# Sheet1.net
KiCad netlist of a schematic drawn in Altium Designer
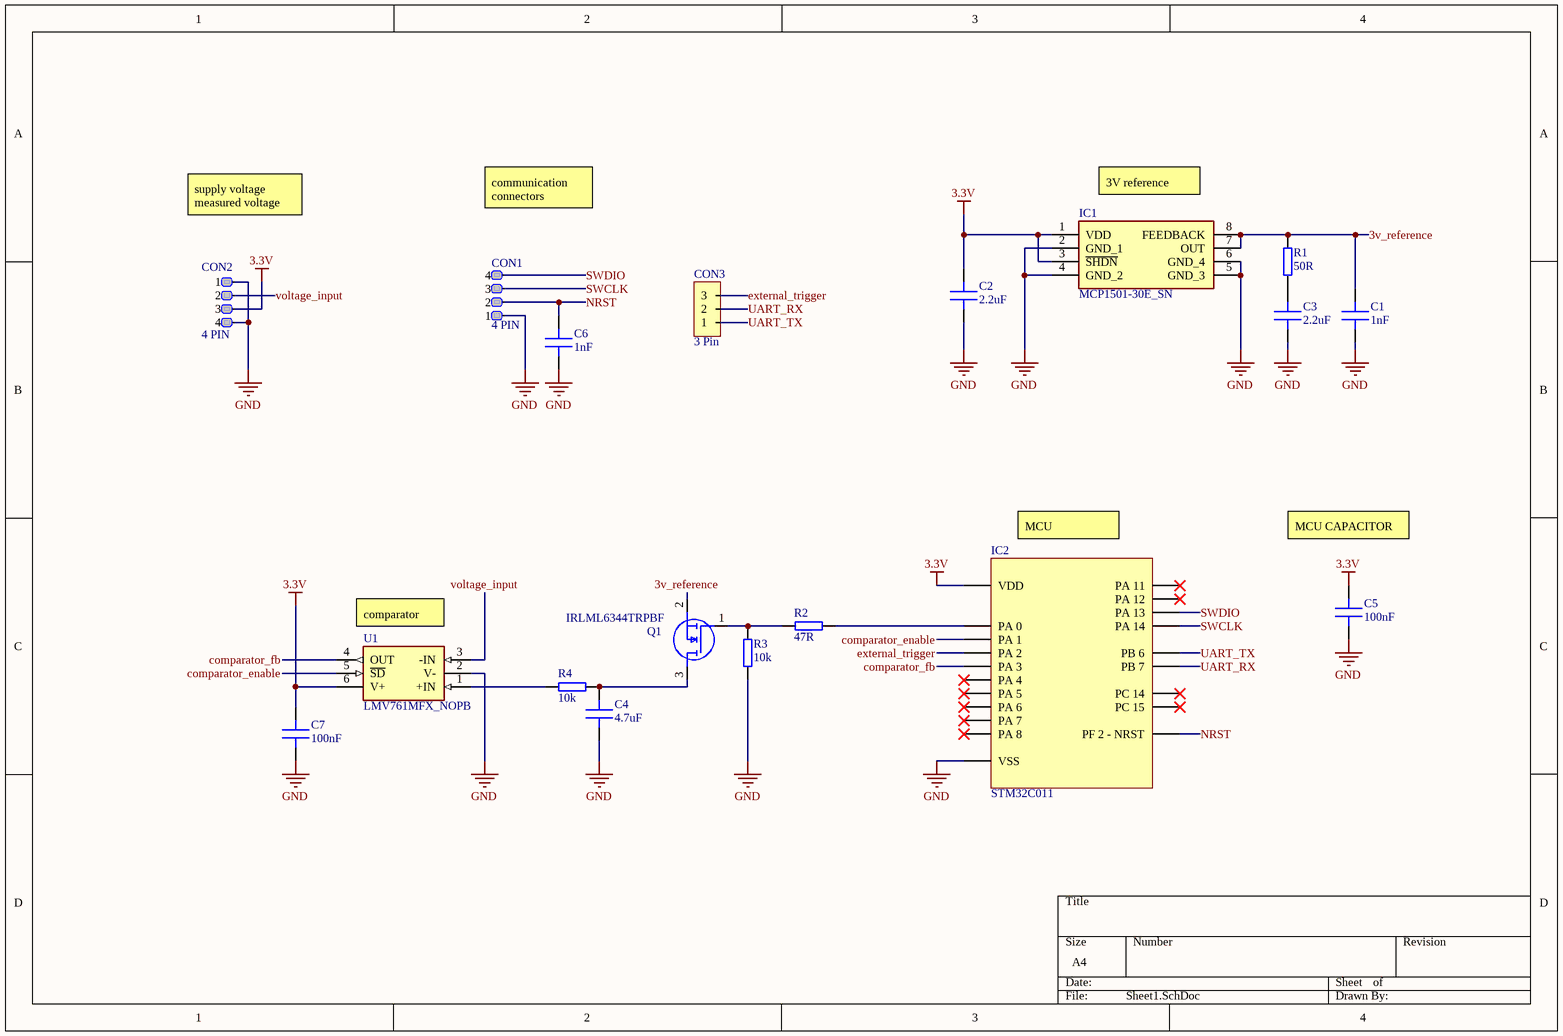
[diagram p0: Sheet1.SchDoc]

(export (version "E")
  (design (tool "Eeschema 10.0.6"))
  (components
    (comp (ref "C1")
      (value "1nF")
      (footprint "C 0402")
      (description "MLCC Capacitor")
      (libsource (lib "Components") (part "Capacitor"))
    )
    (comp (ref "C2")
      (value "2.2uF")
      (footprint "C 0402")
      (description "MLCC Capacitor")
      (libsource (lib "Components") (part "Capacitor"))
    )
    (comp (ref "C3")
      (value "2.2uF")
      (footprint "C 0402")
      (description "MLCC Capacitor")
      (libsource (lib "Components") (part "Capacitor"))
    )
    (comp (ref "C4")
      (value "4.7uF")
      (footprint "C 0402")
      (description "MLCC Capacitor")
      (libsource (lib "Components") (part "Capacitor"))
    )
    (comp (ref "C5")
      (value "100nF")
      (footprint "C 0402")
      (description "MLCC Capacitor")
      (libsource (lib "Components") (part "Capacitor"))
    )
    (comp (ref "C6")
      (value "1nF")
      (footprint "C 0402")
      (description "MLCC Capacitor")
      (libsource (lib "Components") (part "Capacitor"))
    )
    (comp (ref "C7")
      (value "100nF")
      (footprint "C 0402")
      (description "MLCC Capacitor")
      (libsource (lib "Components") (part "Capacitor"))
    )
    (comp (ref "CON1")
      (value "4 PIN")
      (footprint "Goldpin 2.54 4P")
      (libsource (lib "Connectors") (part "4 PIN"))
    )
    (comp (ref "CON2")
      (value "4 PIN")
      (footprint "Goldpin 2.54 4P")
      (libsource (lib "Connectors") (part "4 PIN"))
    )
    (comp (ref "CON3")
      (value "3 Pin")
      (footprint "Goldpin 2.54 3P")
      (libsource (lib "Connectors") (part "3 Pin"))
    )
    (comp (ref "IC1")
      (value "MCP1501-30E_SN")
      (footprint "SamacSys:SOIC127P600X175-8N")
      (description "Integrated Circuit")
      (fields
        (field (name "MANUFACTURER_PART_NUMBER") "MCP1501-30E/SN")
        (field (name "MOUSER PART NUMBER") "579-MCP1501-30E/SN")
      )
      (libsource (lib "*") (part "MCP1501-30E_SN"))
    )
    (comp (ref "IC2")
      (value "STM32C011")
      (footprint "20-UFQFPN")
      (description "UFQFPN 20")
      (libsource (lib "Components") (part "STM32C011F4U"))
    )
    (comp (ref "Q1")
      (value "IRLML6344TRPBF")
      (footprint "SamacSys:SOT95P237X112-3N")
      (description "MOSFET (N-Channel)")
      (fields (field (name "MOUSER PART NUMBER") "942-IRLML6344TRPBF"))
      (libsource (lib "*") (part "IRLML6344TRPBF"))
    )
    (comp (ref "R1")
      (value "50R")
      (footprint "R 0402")
      (description "General pourpouse resistor")
      (libsource (lib "Components") (part "Resistor"))
    )
    (comp (ref "R2")
      (value "47R")
      (footprint "R 0402")
      (description "General pourpouse resistor")
      (libsource (lib "Components") (part "Resistor"))
    )
    (comp (ref "R3")
      (value "10k")
      (footprint "R 0402")
      (description "General pourpouse resistor")
      (libsource (lib "Components") (part "Resistor"))
    )
    (comp (ref "R4")
      (value "10k")
      (footprint "R 0402")
      (description "General pourpouse resistor")
      (libsource (lib "Components") (part "Resistor"))
    )
    (comp (ref "U1")
      (value "LMV761MFX_NOPB")
      (footprint "SamacSys:SOT95P280X145-6N")
      (description "Undefined or Miscellaneous")
      (fields
        (field (name "MANUFACTURER_PART_NUMBER") "LMV761MFX/NOPB")
        (field (name "MOUSER PART NUMBER") "926-LMV761MFX/NOPB")
      )
      (libsource (lib "*") (part "LMV761MFX_NOPB"))
    )
  )
  (nets
    (net (code "1") (name "/3v_reference") (class "Default")
      (node (ref "C1") (pin "1") (pinfunction "1_1") (pintype "passive"))
      (node (ref "IC1") (pin "7") (pinfunction "OUT_7") (pintype "passive"))
      (node (ref "IC1") (pin "8") (pinfunction "FEEDBACK_8") (pintype "passive"))
      (node (ref "Q1") (pin "2") (pinfunction "S_2") (pintype "passive"))
      (node (ref "R1") (pin "2") (pinfunction "2_2") (pintype "passive"))
    )
    (net (code "2") (name "/NRST") (class "Default")
      (node (ref "C6") (pin "1") (pinfunction "1_1") (pintype "passive"))
      (node (ref "CON1") (pin "2") (pinfunction "2_2") (pintype "passive"))
      (node (ref "IC2") (pin "4") (pinfunction "PF_2_-_NRST_4") (pintype "passive"))
    )
    (net (code "3") (name "/SWCLK") (class "Default")
      (node (ref "CON1") (pin "3") (pinfunction "3_3") (pintype "passive"))
      (node (ref "IC2") (pin "17") (pinfunction "PA_14_17") (pintype "passive"))
    )
    (net (code "4") (name "/SWDIO") (class "Default")
      (node (ref "CON1") (pin "4") (pinfunction "4_4") (pintype "passive"))
      (node (ref "IC2") (pin "16") (pinfunction "PA_13_16") (pintype "passive"))
    )
    (net (code "5") (name "/UART_RX") (class "Default")
      (node (ref "CON3") (pin "2") (pinfunction "2_2") (pintype "passive"))
      (node (ref "IC2") (pin "19") (pinfunction "PB_7_19") (pintype "passive"))
    )
    (net (code "6") (name "/UART_TX") (class "Default")
      (node (ref "CON3") (pin "1") (pinfunction "1_1") (pintype "passive"))
      (node (ref "IC2") (pin "18") (pinfunction "PB_6_18") (pintype "passive"))
    )
    (net (code "7") (name "/comparator_enable") (class "Default")
      (node (ref "IC2") (pin "6") (pinfunction "PA_1_6") (pintype "passive"))
      (node (ref "U1") (pin "5") (pinfunction "~{SD}_5") (pintype "input"))
    )
    (net (code "8") (name "/comparator_fb") (class "Default")
      (node (ref "IC2") (pin "8") (pinfunction "PA_3_8") (pintype "passive"))
      (node (ref "U1") (pin "4") (pinfunction "OUT_4") (pintype "output"))
    )
    (net (code "9") (name "/external_trigger") (class "Default")
      (node (ref "CON3") (pin "3") (pinfunction "3_3") (pintype "passive"))
      (node (ref "IC2") (pin "7") (pinfunction "PA_2_7") (pintype "passive"))
    )
    (net (code "10") (name "/voltage_input") (class "Default")
      (node (ref "CON2") (pin "2") (pinfunction "2_2") (pintype "passive"))
      (node (ref "U1") (pin "3") (pinfunction "-IN_3") (pintype "input"))
    )
    (net (code "11") (name "3.3V") (class "Default")
      (node (ref "C2") (pin "1") (pinfunction "1_1") (pintype "passive"))
      (node (ref "C5") (pin "1") (pinfunction "1_1") (pintype "passive"))
      (node (ref "C7") (pin "1") (pinfunction "1_1") (pintype "passive"))
      (node (ref "CON2") (pin "3") (pinfunction "3_3") (pintype "passive"))
      (node (ref "IC1") (pin "1") (pinfunction "VDD_1") (pintype "passive"))
      (node (ref "IC1") (pin "3") (pinfunction "~{SHDN}_3") (pintype "passive"))
      (node (ref "IC2") (pin "2") (pinfunction "VDD_2") (pintype "passive"))
      (node (ref "U1") (pin "6") (pinfunction "V+_6") (pintype "power_in"))
    )
    (net (code "12") (name "GND") (class "Default")
      (node (ref "C1") (pin "2") (pinfunction "2_2") (pintype "passive"))
      (node (ref "C2") (pin "2") (pinfunction "2_2") (pintype "passive"))
      (node (ref "C3") (pin "2") (pinfunction "2_2") (pintype "passive"))
      (node (ref "C4") (pin "2") (pinfunction "2_2") (pintype "passive"))
      (node (ref "C5") (pin "2") (pinfunction "2_2") (pintype "passive"))
      (node (ref "C6") (pin "2") (pinfunction "2_2") (pintype "passive"))
      (node (ref "C7") (pin "2") (pinfunction "2_2") (pintype "passive"))
      (node (ref "CON1") (pin "1") (pinfunction "1_1") (pintype "passive"))
      (node (ref "CON2") (pin "1") (pinfunction "1_1") (pintype "passive"))
      (node (ref "CON2") (pin "4") (pinfunction "4_4") (pintype "passive"))
      (node (ref "IC1") (pin "2") (pinfunction "GND_1_2") (pintype "passive"))
      (node (ref "IC1") (pin "4") (pinfunction "GND_2_4") (pintype "passive"))
      (node (ref "IC1") (pin "5") (pinfunction "GND_3_5") (pintype "passive"))
      (node (ref "IC1") (pin "6") (pinfunction "GND_4_6") (pintype "passive"))
      (node (ref "IC2") (pin "3") (pinfunction "VSS_3") (pintype "passive"))
      (node (ref "R3") (pin "1") (pinfunction "1_1") (pintype "passive"))
      (node (ref "U1") (pin "2") (pinfunction "V-_2") (pintype "power_in"))
    )
    (net (code "13") (name "Net-(C3-Pad1)") (class "Default")
      (node (ref "C3") (pin "1") (pinfunction "1_1") (pintype "passive"))
      (node (ref "R1") (pin "1") (pinfunction "1_1") (pintype "passive"))
    )
    (net (code "14") (name "Net-(IC2-PA_0)") (class "Default")
      (node (ref "IC2") (pin "5") (pinfunction "PA_0_5") (pintype "passive"))
      (node (ref "R2") (pin "1") (pinfunction "1_1") (pintype "passive"))
    )
    (net (code "15") (name "Net-(Q1-D)") (class "Default")
      (node (ref "C4") (pin "1") (pinfunction "1_1") (pintype "passive"))
      (node (ref "Q1") (pin "3") (pinfunction "D_3") (pintype "passive"))
      (node (ref "R4") (pin "2") (pinfunction "2_2") (pintype "passive"))
    )
    (net (code "16") (name "Net-(Q1-G)") (class "Default")
      (node (ref "Q1") (pin "1") (pinfunction "G_1") (pintype "passive"))
      (node (ref "R2") (pin "2") (pinfunction "2_2") (pintype "passive"))
      (node (ref "R3") (pin "2") (pinfunction "2_2") (pintype "passive"))
    )
    (net (code "17") (name "Net-(U1-+IN)") (class "Default")
      (node (ref "R4") (pin "1") (pinfunction "1_1") (pintype "passive"))
      (node (ref "U1") (pin "1") (pinfunction "+IN_1") (pintype "input"))
    )
    (net (code "18") (name "unconnected-(IC2-PA_4-Pad9)") (class "Default")
      (node (ref "IC2") (pin "9") (pinfunction "PA_4_9") (pintype "passive+no_connect"))
    )
    (net (code "19") (name "unconnected-(IC2-PA_5-Pad10)") (class "Default")
      (node (ref "IC2") (pin "10") (pinfunction "PA_5_10") (pintype "passive+no_connect"))
    )
    (net (code "20") (name "unconnected-(IC2-PA_6-Pad11)") (class "Default")
      (node (ref "IC2") (pin "11") (pinfunction "PA_6_11") (pintype "passive+no_connect"))
    )
    (net (code "21") (name "unconnected-(IC2-PA_7-Pad12)") (class "Default")
      (node (ref "IC2") (pin "12") (pinfunction "PA_7_12") (pintype "passive+no_connect"))
    )
    (net (code "22") (name "unconnected-(IC2-PA_8-Pad13)") (class "Default")
      (node (ref "IC2") (pin "13") (pinfunction "PA_8_13") (pintype "passive+no_connect"))
    )
    (net (code "23") (name "unconnected-(IC2-PA_11-Pad14)") (class "Default")
      (node (ref "IC2") (pin "14") (pinfunction "PA_11_14") (pintype "passive+no_connect"))
    )
    (net (code "24") (name "unconnected-(IC2-PA_12-Pad15)") (class "Default")
      (node (ref "IC2") (pin "15") (pinfunction "PA_12_15") (pintype "passive+no_connect"))
    )
    (net (code "25") (name "unconnected-(IC2-PC_14-Pad20)") (class "Default")
      (node (ref "IC2") (pin "20") (pinfunction "PC_14_20") (pintype "passive+no_connect"))
    )
    (net (code "26") (name "unconnected-(IC2-PC_15-Pad1)") (class "Default")
      (node (ref "IC2") (pin "1") (pinfunction "PC_15_1") (pintype "passive+no_connect"))
    )
  )
)
